# GTU-1-V1_1-20160516.net
KiCad netlist of a schematic drawn in Altium Designer
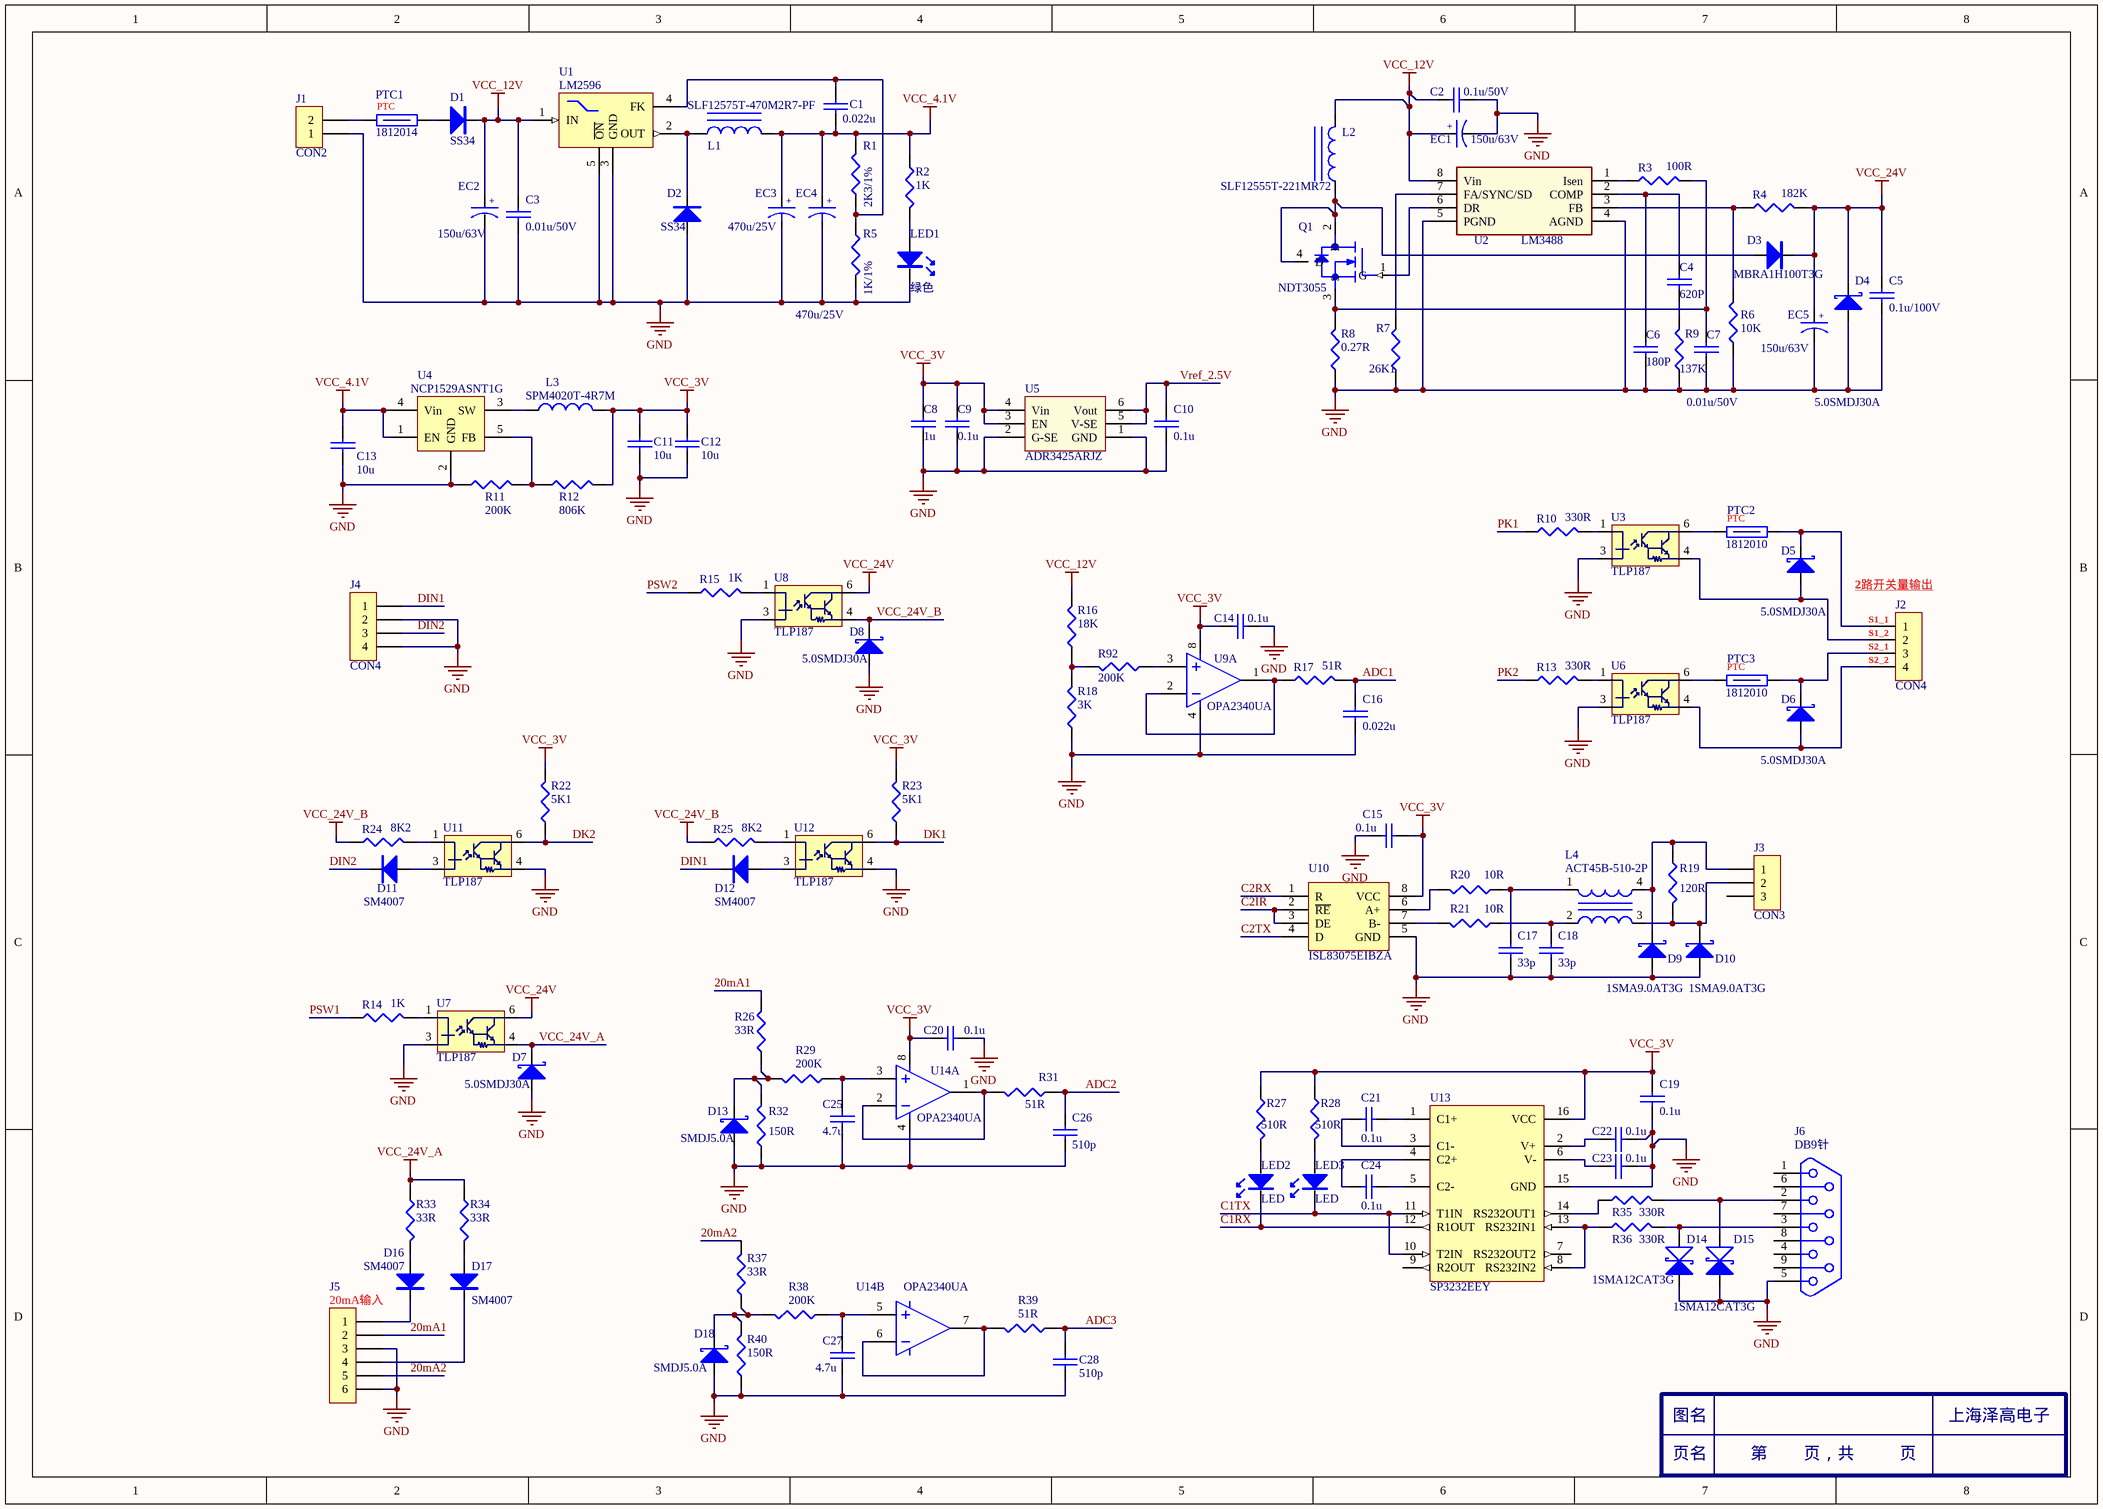
[diagram p0: GTU-1-V1.1-20160516.SCHDOC]

(export (version "E")
  (design (tool "Eeschema 10.0.6"))
  (components
    (comp (ref "3") (value "Component_1") (libsource (lib "*") (part "Component_1")))
    (comp (ref "C1")
      (value "0.022u")
      (footprint "0805-C")
      (description "Capacitor")
      (libsource (lib "STSCH-2012-11-22   ") (part "CAP"))
    )
    (comp (ref "C2")
      (value "0.1u/50V")
      (footprint "0805-C")
      (description "Capacitor")
      (fields (field (name "MFG") "TDK") (field (name "Comment") "0.1u"))
      (libsource (lib "SCHLIB-ZG-2016.01.18      ") (part "CAP"))
    )
    (comp (ref "C3")
      (value "0.01u/50V")
      (footprint "0805-C")
      (description "Capacitor")
      (libsource (lib "*") (part "CAP"))
    )
    (comp (ref "C4")
      (value "620P")
      (footprint "0805-C")
      (description "Capacitor")
      (fields (field (name "MFG") "TDK") (field (name "Comment") "0.1u"))
      (libsource (lib "SCHLIB-ZG-2016.01.18      ") (part "CAP"))
    )
    (comp (ref "C5")
      (value "0.1u/100V")
      (footprint "0805-C")
      (description "Capacitor")
      (fields (field (name "MFG") "TDK") (field (name "Comment") "0.1u"))
      (libsource (lib "SCHLIB-ZG-2016.01.18      ") (part "CAP"))
    )
    (comp (ref "C6")
      (value "180P")
      (footprint "0805-C")
      (description "Capacitor")
      (fields (field (name "MFG") "TDK") (field (name "Comment") "0.1u"))
      (libsource (lib "SCHLIB-ZG-2016.01.18      ") (part "CAP"))
    )
    (comp (ref "C7")
      (value "0.01u/50V")
      (footprint "0805-C")
      (description "Capacitor")
      (fields (field (name "MFG") "TDK") (field (name "Comment") "0.1u"))
      (libsource (lib "SCHLIB-ZG-2016.01.18      ") (part "CAP"))
    )
    (comp (ref "C8")
      (value "1u")
      (footprint "0805-C")
      (description "Capacitor")
      (fields (field (name "MFG") "TDK") (field (name "Comment") "0.1u"))
      (libsource (lib "SCHLIB-ZG-2015.12.11      ") (part "CAP"))
    )
    (comp (ref "C9")
      (value "0.1u")
      (footprint "0805-C")
      (description "Capacitor")
      (fields (field (name "MFG") "TDK"))
      (libsource (lib "SCHLIB-ZG-2015.12.11      ") (part "CAP"))
    )
    (comp (ref "C10")
      (value "0.1u")
      (footprint "0805-C")
      (description "Capacitor")
      (fields (field (name "MFG") "TDK"))
      (libsource (lib "SCHLIB-ZG-2015.12.11      ") (part "CAP"))
    )
    (comp (ref "C11")
      (value "10u")
      (footprint "0805-C")
      (description "Capacitor")
      (libsource (lib "STSCH-2012-08-02  ") (part "CAP"))
    )
    (comp (ref "C12")
      (value "10u")
      (footprint "0805-C")
      (description "Capacitor")
      (libsource (lib "STSCH-2012-08-02  ") (part "CAP"))
    )
    (comp (ref "C13")
      (value "10u")
      (footprint "0805-C")
      (description "Capacitor")
      (libsource (lib "STSCH-2012-02-16  ") (part "CAP"))
    )
    (comp (ref "C14")
      (value "0.1u")
      (footprint "0805-C")
      (description "Capacitor")
      (fields (field (name "MFG") "TDK"))
      (libsource (lib "SCHLIB-ZG-2016.01.18      ") (part "CAP"))
    )
    (comp (ref "C15")
      (value "0.1u")
      (footprint "0805-C")
      (description "Capacitor")
      (libsource (lib "") (part "CAP_1"))
    )
    (comp (ref "C16")
      (value "0.022u")
      (footprint "0805-C")
      (description "Capacitor")
      (fields (field (name "MFG") "TDK") (field (name "Comment") "0.1u"))
      (libsource (lib "SCHLIB-ZG-2016.01.18      ") (part "CAP"))
    )
    (comp (ref "C17")
      (value "33p")
      (footprint "0805-C")
      (description "Capacitor")
      (libsource (lib "STSCH-2013-09-02    ") (part "CAP"))
    )
    (comp (ref "C18")
      (value "33p")
      (footprint "0805-C")
      (description "Capacitor")
      (libsource (lib "STSCH-2013-09-02    ") (part "CAP"))
    )
    (comp (ref "C19")
      (value "0.1u")
      (footprint "0805-C")
      (description "Capacitor")
      (fields (field (name "MFG") "TDK"))
      (libsource (lib "SCHLIB-ZG-2015.12.11      ") (part "CAP"))
    )
    (comp (ref "C20")
      (value "0.1u")
      (footprint "0805-C")
      (description "Capacitor")
      (libsource (lib "STSCH-2011-12-16") (part "CAP"))
    )
    (comp (ref "C21")
      (value "0.1u")
      (footprint "0805-C")
      (description "Capacitor")
      (fields (field (name "MFG") "TDK"))
      (libsource (lib "SCHLIB-ZG-2015.12.11      ") (part "CAP"))
    )
    (comp (ref "C22")
      (value "0.1u")
      (footprint "0805-C")
      (description "Capacitor")
      (fields (field (name "MFG") "TDK"))
      (libsource (lib "SCHLIB-ZG-2015.12.11      ") (part "CAP"))
    )
    (comp (ref "C23")
      (value "0.1u")
      (footprint "0805-C")
      (description "Capacitor")
      (fields (field (name "MFG") "TDK"))
      (libsource (lib "SCHLIB-ZG-2015.12.11      ") (part "CAP"))
    )
    (comp (ref "C24")
      (value "0.1u")
      (footprint "0805-C")
      (description "Capacitor")
      (fields (field (name "MFG") "TDK"))
      (libsource (lib "SCHLIB-ZG-2015.12.11      ") (part "CAP"))
    )
    (comp (ref "C25")
      (value "4.7u")
      (footprint "0805-C")
      (description "Capacitor")
      (libsource (lib "STSCH-2011-12-16") (part "CAP"))
    )
    (comp (ref "C26")
      (value "510p")
      (footprint "0805-C")
      (description "Capacitor")
      (libsource (lib "STSCH-2011-12-16") (part "CAP"))
    )
    (comp (ref "C27")
      (value "4.7u")
      (footprint "0805-C")
      (description "Capacitor")
      (libsource (lib "STSCH-2011-12-16") (part "CAP"))
    )
    (comp (ref "C28")
      (value "510p")
      (footprint "0805-C")
      (description "Capacitor")
      (libsource (lib "STSCH-2011-12-16") (part "CAP"))
    )
    (comp (ref "D1")
      (value "SS34")
      (footprint "SMB")
      (description "Diode")
      (libsource (lib "STSCH-2012-11-08  ") (part "DIODE"))
    )
    (comp (ref "D2")
      (value "SS34")
      (footprint "SMB")
      (description "Diode")
      (libsource (lib "STSCH-2012-11-08  ") (part "DIODE"))
    )
    (comp (ref "D3")
      (value "MBRA1H100T3G")
      (footprint "SMA")
      (description "100V 70mA开关二极管")
      (fields (field (name "MFG") "Verical"))
      (libsource (lib "SCHLIB-ZG-2016.01.18      ") (part "1N4148"))
    )
    (comp (ref "D4")
      (value "5.0SMDJ30A")
      (footprint "SMC")
      (description "bidirectional 5000W TVS")
      (fields (field (name "MFG") "Littelfuse") (field (name "ALTIUM_VALUE") "5.0SMDJ30A"))
      (libsource (lib "SCHLIB-ZG-2016.01.18      ") (part "5.0SMDJxxA"))
    )
    (comp (ref "D5")
      (value "5.0SMDJ30A")
      (footprint "SMC")
      (description "bidirectional 5000W TVS")
      (fields (field (name "MFG") "Littelfuse"))
      (libsource (lib "SCHLIB-ZG-2016.01.18      ") (part "5.0SMDJxxA"))
    )
    (comp (ref "D6")
      (value "5.0SMDJ30A")
      (footprint "SMC")
      (description "bidirectional 5000W TVS")
      (fields (field (name "MFG") "Littelfuse"))
      (libsource (lib "SCHLIB-ZG-2016.01.18      ") (part "5.0SMDJxxA"))
    )
    (comp (ref "D7")
      (value "5.0SMDJ30A")
      (footprint "SMC")
      (description "bidirectional 5000W TVS")
      (fields (field (name "MFG") "Littelfuse"))
      (libsource (lib "SCHLIB-ZG-2016.01.18      ") (part "5.0SMDJxxA"))
    )
    (comp (ref "D8")
      (value "5.0SMDJ30A")
      (footprint "SMC")
      (description "bidirectional 5000W TVS")
      (fields (field (name "MFG") "Littelfuse"))
      (libsource (lib "SCHLIB-ZG-2016.01.18      ") (part "5.0SMDJxxA"))
    )
    (comp (ref "D9")
      (value "1SMAxxAT3G")
      (footprint "SMA")
      (description "Unidirectional 400W TVS")
      (fields (field (name "MFG") "ON-SEMI") (field (name "MFG_PN") "1SMA9.0AT3G"))
      (libsource (lib "SCHLIB-ZG-2016.03.14      ") (part "1SMAxxAT3G"))
    )
    (comp (ref "D10")
      (value "1SMAxxAT3G")
      (footprint "SMA")
      (description "Unidirectional 400W TVS")
      (fields (field (name "MFG") "ON-SEMI") (field (name "MFG_PN") "1SMA9.0AT3G"))
      (libsource (lib "SCHLIB-ZG-2016.03.14      ") (part "1SMAxxAT3G"))
    )
    (comp (ref "D11")
      (value "SM4007")
      (footprint "SMA")
      (description "Diode")
      (libsource (lib "*") (part "SMB"))
    )
    (comp (ref "D12")
      (value "SM4007")
      (footprint "SMA")
      (description "Diode")
      (libsource (lib "*") (part "SMB"))
    )
    (comp (ref "D13")
      (value "SMDJ5.0A")
      (footprint "SMC")
      (libsource (lib "STSCH-2013-02-22   ") (part "TVS"))
    )
    (comp (ref "D14")
      (value "1SMAxxCAT3G")
      (footprint "SMA")
      (description "400W双向TVS  ON Semconductor")
      (fields (field (name "MFG") "ON SEMI") (field (name "MFG-PN") "1SMA12CAT3G"))
      (libsource (lib "SCHLIB-ZG-2015.12.11      ") (part "1SMAxxCAT3G"))
    )
    (comp (ref "D15")
      (value "1SMA12CAT3G")
      (footprint "SMA")
      (description "400W双向TVS  ON Semconductor")
      (fields (field (name "MFG") "ON SEMI"))
      (libsource (lib "SCHLIB-ZG-2015.12.11      ") (part "1SMAxxCAT3G"))
    )
    (comp (ref "D16")
      (value "SM4007")
      (footprint "SMA")
      (description "Diode")
      (libsource (lib "*") (part "SMB"))
    )
    (comp (ref "D17")
      (value "SM4007")
      (footprint "SMA")
      (description "Diode")
      (libsource (lib "*") (part "SMB"))
    )
    (comp (ref "D18")
      (value "SMDJ5.0A")
      (footprint "SMC")
      (libsource (lib "STSCH-2013-02-22   ") (part "TVS"))
    )
    (comp (ref "EC1")
      (value "150u/63V")
      (footprint "SMD10X10.5")
      (description "铝电解电容")
      (fields (field (name "MFG") "RUBYCON"))
      (libsource (lib "SCHLIB-ZG-2015.12.11      ") (part "CAP Al"))
    )
    (comp (ref "EC2")
      (value "150u/63V")
      (footprint "SMD10X10.5")
      (description "铝电解电容")
      (fields (field (name "MFG") "RUBYCON") (field (name "Comment") "CAP Al"))
      (libsource (lib "SCHLIB-ZG-2015.12.11      ") (part "CAP Al"))
    )
    (comp (ref "EC3")
      (value "470u/25V")
      (footprint "SMD10X10.5")
      (libsource (lib "STSCH-2012-11-26   ") (part "CAP Al"))
    )
    (comp (ref "EC4")
      (value "470u/25V")
      (footprint "SMD10X10.5")
      (libsource (lib "STSCH-2012-11-26   ") (part "CAP Al"))
    )
    (comp (ref "EC5")
      (value "150u/63V")
      (footprint "SMD10X10.5")
      (description "铝电解电容")
      (fields (field (name "MFG") "RUBYCON"))
      (libsource (lib "SCHLIB-ZG-2015.12.11      ") (part "CAP Al"))
    )
    (comp (ref "J1")
      (value "CON2")
      (footprint "15EDGRC-3.81-2P")
      (description "Connector")
      (libsource (lib "SCHLIB-ZG-2015.12.11      ") (part "CON2"))
    )
    (comp (ref "J2")
      (value "CON4")
      (footprint "15EDGRC-3.81-4P")
      (description "Connector")
      (libsource (lib "") (part "CON4_1"))
    )
    (comp (ref "J3")
      (value "CON3")
      (footprint "15EDGRC-3.81-3P")
      (description "Connector")
      (libsource (lib "SCHLIB-ZG-2015.12.11      ") (part "CON3"))
    )
    (comp (ref "J4")
      (value "CON4")
      (footprint "15EDGRC-3.81-4P")
      (description "Connector")
      (libsource (lib "SCHLIB-ZG-2016.01.18      ") (part "CON4"))
    )
    (comp (ref "J5")
      (value "20mA输入")
      (footprint "15EDGRC-3.81-6P")
      (description "Connector")
      (libsource (lib "SCHLIB-ZG-2015.12.11      ") (part "CON6"))
    )
    (comp (ref "J6") (value "DB9针") (footprint "DB9RA/M") (libsource (lib "STSCH-2011-12-16") (part "DB9")))
    (comp (ref "L1")
      (value "SLF12575T-470M2R7-PF")
      (footprint "SLF12575")
      (libsource (lib "STSCH-2012-11-22   ") (part "INDUCTOR IRON"))
    )
    (comp (ref "L2")
      (value "SLF12555T-221MR72")
      (footprint "SLF12575")
      (description "12.5X12.5X7.5mm屏蔽功率电感")
      (fields (field (name "MFG") "TDK"))
      (libsource (lib "SCHLIB-ZG-2016.01.18      ") (part "SLF12575"))
    )
    (comp (ref "L3")
      (value "SPM4020T-4R7M")
      (footprint "SPM4020T-4R7M")
      (libsource (lib "STSCH-2012-08-02  ") (part "INDUCTOR"))
    )
    (comp (ref "L4")
      (value "ACT45B-510-2P")
      (footprint "ACT45B")
      (libsource (lib "STSCH-2013-09-02    ") (part "ACT45B-510-2P"))
    )
    (comp (ref "LED1") (value "绿色") (footprint "0805-LED") (libsource (lib "STSCH-20110618Q") (part "LED")))
    (comp (ref "LED2")
      (value "LED")
      (footprint "0805-LED")
      (libsource (lib "SCHLIB-ZG-2015.12.11      ") (part "LED"))
    )
    (comp (ref "LED3")
      (value "LED")
      (footprint "0805-LED")
      (libsource (lib "SCHLIB-ZG-2015.12.11      ") (part "LED"))
    )
    (comp (ref "PTC1")
      (value "1812014")
      (footprint "1812l075")
      (description "自恢复熔丝")
      (fields (field (name "MFG") "君耀"))
      (libsource (lib "SCHLIB-ZG-2016.01.18      ") (part "BK30-500"))
    )
    (comp (ref "PTC2")
      (value "1812010")
      (footprint "1812l075")
      (description "自恢复熔丝")
      (fields (field (name "MFG") "君耀"))
      (libsource (lib "SCHLIB-ZG-2016.01.18      ") (part "BK30-500"))
    )
    (comp (ref "PTC3")
      (value "1812010")
      (footprint "1812l075")
      (description "自恢复熔丝")
      (fields (field (name "MFG") "君耀"))
      (libsource (lib "SCHLIB-ZG-2016.01.18      ") (part "BK30-500"))
    )
    (comp (ref "Q1")
      (value "NDT3055")
      (description "TRANS CAN-N SOT223 2A 60V CMS")
      (fields (field (name "MFG") "FAIRCHILD"))
      (libsource (lib "SCHLIB-ZG-2016.01.18      ") (part "NDT3055"))
    )
    (comp (ref "R1")
      (value "2K3/1%")
      (footprint "0805-R")
      (libsource (lib "STSCH-2012-11-22   ") (part "RES"))
    )
    (comp (ref "R2") (value "1K") (footprint "0805-R") (libsource (lib "STSCH-20110618Q") (part "RES")))
    (comp (ref "R3")
      (value "100R")
      (footprint "0805-R")
      (description "电阻")
      (fields (field (name "MFG") "YAGO") (field (name "Comment") "RES"))
      (libsource (lib "SCHLIB-ZG-2016.01.18      ") (part "RES"))
    )
    (comp (ref "R4")
      (value "182K")
      (footprint "0805-R")
      (description "电阻")
      (fields (field (name "MFG") "YAGO") (field (name "Comment") "RES"))
      (libsource (lib "SCHLIB-ZG-2016.01.18      ") (part "RES"))
    )
    (comp (ref "R5")
      (value "1K/1%")
      (footprint "0805-R")
      (libsource (lib "STSCH-2012-11-22   ") (part "RES"))
    )
    (comp (ref "R6")
      (value "10K")
      (footprint "0805-R")
      (description "电阻")
      (fields (field (name "MFG") "YAGO") (field (name "Comment") "RES"))
      (libsource (lib "SCHLIB-ZG-2016.01.18      ") (part "RES"))
    )
    (comp (ref "R7")
      (value "26K1")
      (footprint "0805-R")
      (description "电阻")
      (fields (field (name "MFG") "YAGO") (field (name "Comment") "RES"))
      (libsource (lib "SCHLIB-ZG-2016.01.18      ") (part "RES"))
    )
    (comp (ref "R8")
      (value "0.27R")
      (footprint "0805-R")
      (description "电阻")
      (fields (field (name "MFG") "YAGO") (field (name "Comment") "RES"))
      (libsource (lib "SCHLIB-ZG-2016.01.18      ") (part "RES"))
    )
    (comp (ref "R9")
      (value "137K")
      (footprint "0805-R")
      (description "电阻")
      (fields (field (name "MFG") "YAGO") (field (name "Comment") "RES"))
      (libsource (lib "SCHLIB-ZG-2016.01.18      ") (part "RES"))
    )
    (comp (ref "R10")
      (value "330R")
      (footprint "0805-R")
      (description "电阻")
      (fields (field (name "MFG") "YAGO") (field (name "Comment") "RES"))
      (libsource (lib "SCHLIB-ZG-2016.01.18      ") (part "RES"))
    )
    (comp (ref "R11") (value "200K") (footprint "0805-R") (libsource (lib "STSCH-2012-08-02  ") (part "RES")))
    (comp (ref "R12") (value "806K") (footprint "0805-R") (libsource (lib "STSCH-2012-08-02  ") (part "RES")))
    (comp (ref "R13")
      (value "330R")
      (footprint "0805-R")
      (description "电阻")
      (fields (field (name "MFG") "YAGO") (field (name "Comment") "RES"))
      (libsource (lib "SCHLIB-ZG-2016.01.18      ") (part "RES"))
    )
    (comp (ref "R14")
      (value "1K")
      (footprint "0805-R")
      (description "电阻")
      (fields (field (name "MFG") "YAGO") (field (name "Comment") "RES"))
      (libsource (lib "SCHLIB-ZG-2016.01.18      ") (part "RES"))
    )
    (comp (ref "R15")
      (value "1K")
      (footprint "0805-R")
      (description "电阻")
      (fields (field (name "MFG") "YAGO") (field (name "Comment") "RES"))
      (libsource (lib "SCHLIB-ZG-2016.01.18      ") (part "RES"))
    )
    (comp (ref "R16")
      (value "18K")
      (footprint "0805-R")
      (description "电阻")
      (fields (field (name "MFG") "YAGO") (field (name "Comment") "RES"))
      (libsource (lib "SCHLIB-ZG-2016.01.18      ") (part "RES"))
    )
    (comp (ref "R17")
      (value "51R")
      (footprint "0805-R")
      (description "电阻")
      (fields (field (name "MFG") "YAGO") (field (name "Comment") "RES"))
      (libsource (lib "SCHLIB-ZG-2016.01.18      ") (part "RES"))
    )
    (comp (ref "R18")
      (value "3K")
      (footprint "0805-R")
      (description "电阻")
      (fields (field (name "MFG") "YAGO") (field (name "Comment") "RES"))
      (libsource (lib "SCHLIB-ZG-2016.01.18      ") (part "RES"))
    )
    (comp (ref "R19")
      (value "120R")
      (footprint "1210-R")
      (libsource (lib "STSCH-2013-09-02    ") (part "RES"))
    )
    (comp (ref "R20")
      (value "10R")
      (footprint "0805-R")
      (libsource (lib "STSCH-2013-09-02    ") (part "RES"))
    )
    (comp (ref "R21")
      (value "10R")
      (footprint "0805-R")
      (libsource (lib "STSCH-2013-09-02    ") (part "RES"))
    )
    (comp (ref "R22")
      (value "5K1")
      (footprint "0805-R")
      (description "电阻")
      (fields (field (name "MFG") "YAGO") (field (name "Comment") "RES"))
      (libsource (lib "SCHLIB-ZG-2016.01.18      ") (part "RES"))
    )
    (comp (ref "R23")
      (value "5K1")
      (footprint "0805-R")
      (description "电阻")
      (fields (field (name "MFG") "YAGO") (field (name "Comment") "RES"))
      (libsource (lib "SCHLIB-ZG-2016.01.18      ") (part "RES"))
    )
    (comp (ref "R24")
      (value "8K2")
      (footprint "0805-R")
      (description "电阻")
      (fields (field (name "MFG") "YAGO") (field (name "Comment") "RES"))
      (libsource (lib "SCHLIB-ZG-2016.01.18      ") (part "RES"))
    )
    (comp (ref "R25")
      (value "8K2")
      (footprint "0805-R")
      (description "电阻")
      (fields (field (name "MFG") "YAGO") (field (name "Comment") "RES"))
      (libsource (lib "SCHLIB-ZG-2016.01.18      ") (part "RES"))
    )
    (comp (ref "R26") (value "33R") (footprint "1210-R") (libsource (lib "STSCH-2011-12-16") (part "RES")))
    (comp (ref "R27")
      (value "510R")
      (footprint "0805-R")
      (description "电阻")
      (fields (field (name "MFG") "YAGO") (field (name "Comment") "RES"))
      (libsource (lib "SCHLIB-ZG-2016.01.18      ") (part "RES"))
    )
    (comp (ref "R28")
      (value "510R")
      (footprint "0805-R")
      (description "电阻")
      (fields (field (name "MFG") "YAGO") (field (name "Comment") "RES"))
      (libsource (lib "SCHLIB-ZG-2016.01.18      ") (part "RES"))
    )
    (comp (ref "R29") (value "200K") (footprint "0805-R") (libsource (lib "STSCH-2011-12-16") (part "RES")))
    (comp (ref "R31") (value "51R") (footprint "0805-R") (libsource (lib "STSCH-2011-12-16") (part "RES")))
    (comp (ref "R32") (value "150R") (footprint "1210-R") (libsource (lib "STSCH-2011-12-16") (part "RES")))
    (comp (ref "R33")
      (value "33R")
      (footprint "1210-R")
      (libsource (lib "STSCH-2013-09-02    ") (part "RES"))
    )
    (comp (ref "R34")
      (value "33R")
      (footprint "1210-R")
      (libsource (lib "STSCH-2013-09-02    ") (part "RES"))
    )
    (comp (ref "R35")
      (value "330R")
      (footprint "0805-R")
      (description "电阻")
      (fields (field (name "MFG") "YAGO") (field (name "Comment") "RES"))
      (libsource (lib "SCHLIB-ZG-2015.12.11      ") (part "RES"))
    )
    (comp (ref "R36")
      (value "330R")
      (footprint "0805-R")
      (description "电阻")
      (fields (field (name "MFG") "YAGO") (field (name "Comment") "RES"))
      (libsource (lib "SCHLIB-ZG-2015.12.11      ") (part "RES"))
    )
    (comp (ref "R37") (value "33R") (footprint "1210-R") (libsource (lib "STSCH-2011-12-16") (part "RES")))
    (comp (ref "R38") (value "200K") (footprint "0805-R") (libsource (lib "STSCH-2011-12-16") (part "RES")))
    (comp (ref "R39") (value "51R") (footprint "0805-R") (libsource (lib "STSCH-2011-12-16") (part "RES")))
    (comp (ref "R40") (value "150R") (footprint "1210-R") (libsource (lib "STSCH-2011-12-16") (part "RES")))
    (comp (ref "R92")
      (value "200K")
      (footprint "0805-R")
      (description "电阻")
      (fields (field (name "MFG") "YAGO") (field (name "Comment") "RES"))
      (libsource (lib "SCHLIB-ZG-2016.01.18      ") (part "RES"))
    )
    (comp (ref "U1")
      (value "LM2596")
      (footprint "D2PAK-5")
      (libsource (lib "STSCH-2012-11-22   ") (part "LM2596DSADJR4G"))
    )
    (comp (ref "U2")
      (value "LM3488")
      (description "ANALOG LM3488MM CMS")
      (fields (field (name "MFG") "NATIONAL SEMI"))
      (libsource (lib "SCHLIB-ZG-2016.01.18      ") (part "LM3488MM NOPB"))
    )
    (comp (ref "U3")
      (value "TLP187")
      (footprint "TLP187")
      (description "Darlington Photocouple Trsnsistor")
      (fields (field (name "MFG") "TOSHIBA"))
      (libsource (lib "SCHLIB-ZG-2016.01.18      ") (part "TLP187"))
    )
    (comp (ref "U4")
      (value "NCP1529ASNT1G")
      (footprint "SOT-23-5")
      (libsource (lib "STSCH-2012-08-02  ") (part "NCP1529ASNT1G"))
    )
    (comp (ref "U5")
      (value "ADR3425ARJZ")
      (footprint "SOT-23-6")
      (libsource (lib "轨旁检测-20151210") (part "ADR3430ARJZ"))
    )
    (comp (ref "U6")
      (value "TLP187")
      (footprint "TLP187")
      (description "Darlington Photocouple Trsnsistor")
      (fields (field (name "MFG") "TOSHIBA"))
      (libsource (lib "SCHLIB-ZG-2016.01.18      ") (part "TLP187"))
    )
    (comp (ref "U7")
      (value "TLP187")
      (footprint "TLP187")
      (description "Darlington Photocouple Trsnsistor")
      (fields (field (name "MFG") "TOSHIBA"))
      (libsource (lib "SCHLIB-ZG-2016.01.18      ") (part "TLP187"))
    )
    (comp (ref "U8")
      (value "TLP187")
      (footprint "TLP187")
      (description "Darlington Photocouple Trsnsistor")
      (fields (field (name "MFG") "TOSHIBA"))
      (libsource (lib "SCHLIB-ZG-2016.01.18      ") (part "TLP187"))
    )
    (comp (ref "U9")
      (value "OPA2340UA")
      (footprint "SO-8")
      (description "microPower, Rail-to-Rail  2 Operational Amplifiers")
      (fields (field (name "MFG") "TI"))
      (libsource (lib "SCHLIB-ZG-2016.01.18      ") (part "OPA2340"))
    )
    (comp (ref "U10") (value "ISL83075EIBZA") (footprint "SO-8") (libsource (lib "*") (part "75LBC184")))
    (comp (ref "U11")
      (value "TLP187")
      (footprint "TLP187")
      (description "Darlington Photocouple Trsnsistor")
      (fields (field (name "MFG") "TOSHIBA"))
      (libsource (lib "SCHLIB-ZG-2016.01.18      ") (part "TLP187"))
    )
    (comp (ref "U12")
      (value "TLP187")
      (footprint "TLP187")
      (description "Darlington Photocouple Trsnsistor")
      (fields (field (name "MFG") "TOSHIBA"))
      (libsource (lib "SCHLIB-ZG-2016.01.18      ") (part "TLP187"))
    )
    (comp (ref "U13")
      (value "SP3232EEY")
      (footprint "TSSOP-16")
      (description "+3.3V 1Mbps RS232收发器 SIPEX")
      (fields (field (name "MFG") "SIPEX"))
      (libsource (lib "SCHLIB-ZG-2015.12.11      ") (part "SP3232EEA"))
    )
    (comp (ref "U14")
      (value "OPA2340UA")
      (footprint "SO-8")
      (description "microPower, Rail-to-Rail  2 Operational Amplifiers")
      (fields (field (name "MFG") "TI"))
      (libsource (lib "SCHLIB-ZG-2016.01.18      ") (part "OPA2340"))
    )
  )
  (nets
    (net (code "1") (name "/20mA1") (class "Default")
      (node (ref "J5") (pin "2") (pinfunction "2_2") (pintype "passive"))
      (node (ref "R26") (pin "2") (pinfunction "2_2") (pintype "passive"))
    )
    (net (code "2") (name "/20mA2") (class "Default")
      (node (ref "J5") (pin "5") (pinfunction "5_5") (pintype "passive"))
      (node (ref "R37") (pin "2") (pinfunction "2_2") (pintype "passive"))
    )
    (net (code "3") (name "/ADC1") (class "Default")
      (node (ref "C16") (pin "1") (pinfunction "1_1") (pintype "passive"))
      (node (ref "R17") (pin "2") (pinfunction "2_2") (pintype "passive"))
    )
    (net (code "4") (name "/ADC2") (class "Default")
      (node (ref "C26") (pin "1") (pinfunction "1_1") (pintype "passive"))
      (node (ref "R31") (pin "1") (pinfunction "1_1") (pintype "passive"))
    )
    (net (code "5") (name "/ADC3") (class "Default")
      (node (ref "C28") (pin "1") (pinfunction "1_1") (pintype "passive"))
      (node (ref "R39") (pin "1") (pinfunction "1_1") (pintype "passive"))
    )
    (net (code "6") (name "/C1RX") (class "Default")
      (node (ref "LED2") (pin "2") (pintype "passive"))
      (node (ref "U13") (pin "12") (pinfunction "R1OUT_12") (pintype "output"))
    )
    (net (code "7") (name "/C1TX") (class "Default")
      (node (ref "LED3") (pin "2") (pintype "passive"))
      (node (ref "U13") (pin "10") (pinfunction "T2IN_10") (pintype "input"))
      (node (ref "U13") (pin "11") (pinfunction "T1IN_11") (pintype "input"))
    )
    (net (code "8") (name "/C2IR") (class "Default")
      (node (ref "U10") (pin "2") (pinfunction "~{RE}_2") (pintype "passive"))
      (node (ref "U10") (pin "3") (pinfunction "DE_3") (pintype "passive"))
    )
    (net (code "9") (name "/C2RX") (class "Default")
      (node (ref "U10") (pin "1") (pinfunction "R_1") (pintype "passive"))
    )
    (net (code "10") (name "/C2TX") (class "Default")
      (node (ref "U10") (pin "4") (pinfunction "D_4") (pintype "passive"))
    )
    (net (code "11") (name "/DIN1") (class "Default")
      (node (ref "D12") (pin "K") (pinfunction "K_K") (pintype "passive"))
      (node (ref "J4") (pin "1") (pinfunction "1_1") (pintype "passive"))
    )
    (net (code "12") (name "/DIN2") (class "Default")
      (node (ref "D11") (pin "K") (pinfunction "K_K") (pintype "passive"))
      (node (ref "J4") (pin "3") (pinfunction "3_3") (pintype "passive"))
    )
    (net (code "13") (name "/DK1") (class "Default")
      (node (ref "R23") (pin "1") (pinfunction "1_1") (pintype "passive"))
      (node (ref "U12") (pin "6") (pinfunction "6_6") (pintype "passive"))
    )
    (net (code "14") (name "/DK2") (class "Default")
      (node (ref "R22") (pin "1") (pinfunction "1_1") (pintype "passive"))
      (node (ref "U11") (pin "6") (pinfunction "6_6") (pintype "passive"))
    )
    (net (code "15") (name "/PK1") (class "Default")
      (node (ref "R10") (pin "1") (pinfunction "1_1") (pintype "passive"))
    )
    (net (code "16") (name "/PK2") (class "Default")
      (node (ref "R13") (pin "1") (pinfunction "1_1") (pintype "passive"))
    )
    (net (code "17") (name "/PSW1") (class "Default")
      (node (ref "R14") (pin "1") (pinfunction "1_1") (pintype "passive"))
    )
    (net (code "18") (name "/PSW2") (class "Default")
      (node (ref "R15") (pin "1") (pinfunction "1_1") (pintype "passive"))
    )
    (net (code "19") (name "/Vref_2.5V") (class "Default")
      (node (ref "C10") (pin "1") (pinfunction "1_1") (pintype "passive"))
      (node (ref "U5") (pin "5") (pinfunction "V-SE_5") (pintype "passive"))
      (node (ref "U5") (pin "6") (pinfunction "Vout_6") (pintype "passive"))
    )
    (net (code "20") (name "GND") (class "Default")
      (node (ref "C10") (pin "2") (pinfunction "2_2") (pintype "passive"))
      (node (ref "C11") (pin "2") (pinfunction "2_2") (pintype "passive"))
      (node (ref "C12") (pin "2") (pinfunction "2_2") (pintype "passive"))
      (node (ref "C13") (pin "2") (pinfunction "2_2") (pintype "passive"))
      (node (ref "C14") (pin "2") (pinfunction "2_2") (pintype "passive"))
      (node (ref "C15") (pin "2") (pinfunction "2_2") (pintype "passive"))
      (node (ref "C16") (pin "2") (pinfunction "2_2") (pintype "passive"))
      (node (ref "C17") (pin "2") (pinfunction "2_2") (pintype "passive"))
      (node (ref "C18") (pin "2") (pinfunction "2_2") (pintype "passive"))
      (node (ref "C19") (pin "1") (pinfunction "1_1") (pintype "passive"))
      (node (ref "C2") (pin "2") (pinfunction "2_2") (pintype "passive"))
      (node (ref "C20") (pin "2") (pinfunction "2_2") (pintype "passive"))
      (node (ref "C22") (pin "1") (pinfunction "1_1") (pintype "passive"))
      (node (ref "C23") (pin "1") (pinfunction "1_1") (pintype "passive"))
      (node (ref "C25") (pin "2") (pinfunction "2_2") (pintype "passive"))
      (node (ref "C26") (pin "2") (pinfunction "2_2") (pintype "passive"))
      (node (ref "C27") (pin "2") (pinfunction "2_2") (pintype "passive"))
      (node (ref "C28") (pin "2") (pinfunction "2_2") (pintype "passive"))
      (node (ref "C3") (pin "2") (pinfunction "2_2") (pintype "passive"))
      (node (ref "C5") (pin "2") (pinfunction "2_2") (pintype "passive"))
      (node (ref "C6") (pin "2") (pinfunction "2_2") (pintype "passive"))
      (node (ref "C7") (pin "2") (pinfunction "2_2") (pintype "passive"))
      (node (ref "C8") (pin "2") (pinfunction "2_2") (pintype "passive"))
      (node (ref "C9") (pin "2") (pinfunction "2_2") (pintype "passive"))
      (node (ref "D10") (pin "A") (pinfunction "A_A") (pintype "passive"))
      (node (ref "D13") (pin "A") (pinfunction "A_A") (pintype "passive"))
      (node (ref "D14") (pin "A") (pinfunction "A_A") (pintype "passive"))
      (node (ref "D15") (pin "A") (pinfunction "A_A") (pintype "passive"))
      (node (ref "D18") (pin "A") (pinfunction "A_A") (pintype "passive"))
      (node (ref "D2") (pin "A") (pinfunction "A_A") (pintype "passive"))
      (node (ref "D4") (pin "A") (pinfunction "A_A") (pintype "passive"))
      (node (ref "D7") (pin "A") (pinfunction "A_A") (pintype "passive"))
      (node (ref "D8") (pin "A") (pinfunction "A_A") (pintype "passive"))
      (node (ref "D9") (pin "A") (pinfunction "A_A") (pintype "passive"))
      (node (ref "EC1") (pin "2") (pinfunction "2_2") (pintype "passive"))
      (node (ref "EC2") (pin "2") (pinfunction "2_2") (pintype "passive"))
      (node (ref "EC3") (pin "2") (pinfunction "2_2") (pintype "passive"))
      (node (ref "EC4") (pin "2") (pinfunction "2_2") (pintype "passive"))
      (node (ref "EC5") (pin "2") (pinfunction "2_2") (pintype "passive"))
      (node (ref "J1") (pin "1") (pinfunction "1_1") (pintype "passive"))
      (node (ref "J4") (pin "2") (pinfunction "2_2") (pintype "passive"))
      (node (ref "J4") (pin "4") (pinfunction "4_4") (pintype "passive"))
      (node (ref "J5") (pin "3") (pinfunction "3_3") (pintype "passive"))
      (node (ref "J5") (pin "6") (pinfunction "6_6") (pintype "passive"))
      (node (ref "J6") (pin "5") (pinfunction "5_5") (pintype "passive"))
      (node (ref "LED1") (pin "2") (pintype "passive"))
      (node (ref "R11") (pin "1") (pinfunction "1_1") (pintype "passive"))
      (node (ref "R18") (pin "1") (pinfunction "1_1") (pintype "passive"))
      (node (ref "R32") (pin "1") (pinfunction "1_1") (pintype "passive"))
      (node (ref "R40") (pin "1") (pinfunction "1_1") (pintype "passive"))
      (node (ref "R5") (pin "2") (pinfunction "2_2") (pintype "passive"))
      (node (ref "R6") (pin "1") (pinfunction "1_1") (pintype "passive"))
      (node (ref "R7") (pin "1") (pinfunction "1_1") (pintype "passive"))
      (node (ref "R8") (pin "1") (pinfunction "1_1") (pintype "passive"))
      (node (ref "R9") (pin "1") (pinfunction "1_1") (pintype "passive"))
      (node (ref "U1") (pin "3") (pinfunction "GND_3") (pintype "passive"))
      (node (ref "U1") (pin "5") (pinfunction "~{ON}_5") (pintype "passive"))
      (node (ref "U10") (pin "5") (pinfunction "GND_5") (pintype "power_in"))
      (node (ref "U11") (pin "4") (pinfunction "4_4") (pintype "passive"))
      (node (ref "U12") (pin "4") (pinfunction "4_4") (pintype "passive"))
      (node (ref "U13") (pin "15") (pinfunction "GND_15") (pintype "power_in"))
      (node (ref "U14") (pin "4") (pintype "passive"))
      (node (ref "U2") (pin "4") (pinfunction "AGND_4") (pintype "power_in"))
      (node (ref "U2") (pin "5") (pinfunction "PGND_5") (pintype "power_in"))
      (node (ref "U3") (pin "3") (pinfunction "3_3") (pintype "passive"))
      (node (ref "U4") (pin "2") (pinfunction "GND_2") (pintype "passive"))
      (node (ref "U5") (pin "1") (pinfunction "GND_1") (pintype "passive"))
      (node (ref "U5") (pin "2") (pinfunction "G-SE_2") (pintype "passive"))
      (node (ref "U6") (pin "3") (pinfunction "3_3") (pintype "passive"))
      (node (ref "U7") (pin "3") (pinfunction "3_3") (pintype "passive"))
      (node (ref "U8") (pin "3") (pinfunction "3_3") (pintype "passive"))
      (node (ref "U9") (pin "4") (pintype "passive"))
    )
    (net (code "21") (name "Net-(C4-Pad2)") (class "Default")
      (node (ref "C4") (pin "2") (pinfunction "2_2") (pintype "passive"))
      (node (ref "R9") (pin "2") (pinfunction "2_2") (pintype "passive"))
    )
    (net (code "22") (name "Net-(C17-Pad1)") (class "Default")
      (node (ref "C17") (pin "1") (pinfunction "1_1") (pintype "passive"))
      (node (ref "L4") (pin "1") (pinfunction "1_1") (pintype "passive"))
      (node (ref "R20") (pin "1") (pinfunction "1_1") (pintype "passive"))
    )
    (net (code "23") (name "Net-(C18-Pad1)") (class "Default")
      (node (ref "C18") (pin "1") (pinfunction "1_1") (pintype "passive"))
      (node (ref "L4") (pin "2") (pinfunction "2_2") (pintype "passive"))
      (node (ref "R21") (pin "1") (pinfunction "1_1") (pintype "passive"))
    )
    (net (code "24") (name "Net-(C25-Pad1)") (class "Default")
      (node (ref "C25") (pin "1") (pinfunction "1_1") (pintype "passive"))
      (node (ref "R29") (pin "1") (pinfunction "1_1") (pintype "passive"))
      (node (ref "U14") (pin "3") (pintype "passive"))
    )
    (net (code "25") (name "Net-(C27-Pad1)") (class "Default")
      (node (ref "C27") (pin "1") (pinfunction "1_1") (pintype "passive"))
      (node (ref "R38") (pin "1") (pinfunction "1_1") (pintype "passive"))
      (node (ref "U14") (pin "5") (pintype "passive"))
    )
    (net (code "26") (name "Net-(D1-PadA)") (class "Default")
      (node (ref "D1") (pin "A") (pinfunction "A_A") (pintype "passive"))
      (node (ref "PTC1") (pin "2") (pinfunction "2_2") (pintype "passive"))
    )
    (net (code "27") (name "Net-(D3-PadA)") (class "Default")
      (node (ref "D3") (pin "A") (pinfunction "A_A") (pintype "passive"))
      (node (ref "L2") (pin "1") (pinfunction "1_1") (pintype "passive"))
      (node (ref "Q1") (pin "2") (pinfunction "D_2") (pintype "power_in"))
      (node (ref "Q1") (pin "4") (pinfunction "D_4") (pintype "power_in"))
    )
    (net (code "28") (name "Net-(D5-PadA)") (class "Default")
      (node (ref "D5") (pin "A") (pinfunction "A_A") (pintype "passive"))
      (node (ref "J2") (pin "2") (pinfunction "2_2") (pintype "passive"))
      (node (ref "U3") (pin "4") (pinfunction "4_4") (pintype "passive"))
    )
    (net (code "29") (name "Net-(D5-PadK)") (class "Default")
      (node (ref "D5") (pin "K") (pinfunction "K_K") (pintype "passive"))
      (node (ref "J2") (pin "1") (pinfunction "1_1") (pintype "passive"))
      (node (ref "PTC2") (pin "2") (pinfunction "2_2") (pintype "passive"))
    )
    (net (code "30") (name "Net-(D6-PadA)") (class "Default")
      (node (ref "D6") (pin "A") (pinfunction "A_A") (pintype "passive"))
      (node (ref "J2") (pin "4") (pinfunction "4_4") (pintype "passive"))
      (node (ref "U6") (pin "4") (pinfunction "4_4") (pintype "passive"))
    )
    (net (code "31") (name "Net-(D6-PadK)") (class "Default")
      (node (ref "D6") (pin "K") (pinfunction "K_K") (pintype "passive"))
      (node (ref "J2") (pin "3") (pinfunction "3_3") (pintype "passive"))
      (node (ref "PTC3") (pin "2") (pinfunction "2_2") (pintype "passive"))
    )
    (net (code "32") (name "Net-(D9-PadK)") (class "Default")
      (node (ref "D9") (pin "K") (pinfunction "K_K") (pintype "passive"))
      (node (ref "J3") (pin "1") (pinfunction "1_1") (pintype "passive"))
      (node (ref "L4") (pin "4") (pinfunction "4_4") (pintype "passive"))
      (node (ref "R19") (pin "1") (pinfunction "1_1") (pintype "passive"))
    )
    (net (code "33") (name "Net-(D10-PadK)") (class "Default")
      (node (ref "D10") (pin "K") (pinfunction "K_K") (pintype "passive"))
      (node (ref "J3") (pin "2") (pinfunction "2_2") (pintype "passive"))
      (node (ref "L4") (pin "3") (pinfunction "3_3") (pintype "passive"))
      (node (ref "R19") (pin "2") (pinfunction "2_2") (pintype "passive"))
    )
    (net (code "34") (name "Net-(D11-PadA)") (class "Default")
      (node (ref "D11") (pin "A") (pinfunction "A_A") (pintype "passive"))
      (node (ref "U11") (pin "3") (pinfunction "3_3") (pintype "passive"))
    )
    (net (code "35") (name "Net-(D12-PadA)") (class "Default")
      (node (ref "D12") (pin "A") (pinfunction "A_A") (pintype "passive"))
      (node (ref "U12") (pin "3") (pinfunction "3_3") (pintype "passive"))
    )
    (net (code "36") (name "Net-(D13-PadK)") (class "Default")
      (node (ref "D13") (pin "K") (pinfunction "K_K") (pintype "passive"))
      (node (ref "R26") (pin "1") (pinfunction "1_1") (pintype "passive"))
      (node (ref "R29") (pin "2") (pinfunction "2_2") (pintype "passive"))
      (node (ref "R32") (pin "2") (pinfunction "2_2") (pintype "passive"))
    )
    (net (code "37") (name "Net-(D14-PadK)") (class "Default")
      (node (ref "D14") (pin "K") (pinfunction "K_K") (pintype "passive"))
      (node (ref "J6") (pin "3") (pinfunction "3_3") (pintype "passive"))
      (node (ref "R36") (pin "1") (pinfunction "1_1") (pintype "passive"))
    )
    (net (code "38") (name "Net-(D15-PadK)") (class "Default")
      (node (ref "D15") (pin "K") (pinfunction "K_K") (pintype "passive"))
      (node (ref "J6") (pin "2") (pinfunction "2_2") (pintype "passive"))
      (node (ref "R35") (pin "1") (pinfunction "1_1") (pintype "passive"))
    )
    (net (code "39") (name "Net-(D16-PadA)") (class "Default")
      (node (ref "D16") (pin "A") (pinfunction "A_A") (pintype "passive"))
      (node (ref "R33") (pin "2") (pinfunction "2_2") (pintype "passive"))
    )
    (net (code "40") (name "Net-(D16-PadK)") (class "Default")
      (node (ref "D16") (pin "K") (pinfunction "K_K") (pintype "passive"))
      (node (ref "J5") (pin "1") (pinfunction "1_1") (pintype "passive"))
    )
    (net (code "41") (name "Net-(D17-PadA)") (class "Default")
      (node (ref "D17") (pin "A") (pinfunction "A_A") (pintype "passive"))
      (node (ref "R34") (pin "2") (pinfunction "2_2") (pintype "passive"))
    )
    (net (code "42") (name "Net-(D17-PadK)") (class "Default")
      (node (ref "D17") (pin "K") (pinfunction "K_K") (pintype "passive"))
      (node (ref "J5") (pin "4") (pinfunction "4_4") (pintype "passive"))
    )
    (net (code "43") (name "Net-(D18-PadK)") (class "Default")
      (node (ref "D18") (pin "K") (pinfunction "K_K") (pintype "passive"))
      (node (ref "R37") (pin "1") (pinfunction "1_1") (pintype "passive"))
      (node (ref "R38") (pin "2") (pinfunction "2_2") (pintype "passive"))
      (node (ref "R40") (pin "2") (pinfunction "2_2") (pintype "passive"))
    )
    (net (code "44") (name "Net-(J1-Pad2)") (class "Default")
      (node (ref "J1") (pin "2") (pinfunction "2_2") (pintype "passive"))
      (node (ref "PTC1") (pin "1") (pinfunction "1_1") (pintype "passive"))
    )
    (net (code "45") (name "Net-(LED1-Pad1)") (class "Default")
      (node (ref "LED1") (pin "1") (pintype "passive"))
      (node (ref "R2") (pin "2") (pinfunction "2_2") (pintype "passive"))
    )
    (net (code "46") (name "Net-(LED2-Pad1)") (class "Default")
      (node (ref "LED2") (pin "1") (pintype "passive"))
      (node (ref "R27") (pin "1") (pinfunction "1_1") (pintype "passive"))
    )
    (net (code "47") (name "Net-(LED3-Pad1)") (class "Default")
      (node (ref "LED3") (pin "1") (pintype "passive"))
      (node (ref "R28") (pin "1") (pinfunction "1_1") (pintype "passive"))
    )
    (net (code "48") (name "Net-(PTC2-Pad1)") (class "Default")
      (node (ref "PTC2") (pin "1") (pinfunction "1_1") (pintype "passive"))
      (node (ref "U3") (pin "6") (pinfunction "6_6") (pintype "passive"))
    )
    (net (code "49") (name "Net-(PTC3-Pad1)") (class "Default")
      (node (ref "PTC3") (pin "1") (pinfunction "1_1") (pintype "passive"))
      (node (ref "U6") (pin "6") (pinfunction "6_6") (pintype "passive"))
    )
    (net (code "50") (name "Net-(Q1-G)") (class "Default")
      (node (ref "Q1") (pin "1") (pinfunction "G_1") (pintype "input"))
      (node (ref "U2") (pin "6") (pinfunction "DR_6") (pintype "passive"))
    )
    (net (code "51") (name "Net-(Q1-S)") (class "Default")
      (node (ref "C7") (pin "1") (pinfunction "1_1") (pintype "passive"))
      (node (ref "Q1") (pin "3") (pinfunction "S_3") (pintype "passive"))
      (node (ref "R3") (pin "2") (pinfunction "2_2") (pintype "passive"))
      (node (ref "R8") (pin "2") (pinfunction "2_2") (pintype "passive"))
    )
    (net (code "52") (name "Net-(R10-Pad2)") (class "Default")
      (node (ref "R10") (pin "2") (pinfunction "2_2") (pintype "passive"))
      (node (ref "U3") (pin "1") (pinfunction "1_1") (pintype "passive"))
    )
    (net (code "53") (name "Net-(R13-Pad2)") (class "Default")
      (node (ref "R13") (pin "2") (pinfunction "2_2") (pintype "passive"))
      (node (ref "U6") (pin "1") (pinfunction "1_1") (pintype "passive"))
    )
    (net (code "54") (name "Net-(R14-Pad2)") (class "Default")
      (node (ref "R14") (pin "2") (pinfunction "2_2") (pintype "passive"))
      (node (ref "U7") (pin "1") (pinfunction "1_1") (pintype "passive"))
    )
    (net (code "55") (name "Net-(R15-Pad2)") (class "Default")
      (node (ref "R15") (pin "2") (pinfunction "2_2") (pintype "passive"))
      (node (ref "U8") (pin "1") (pinfunction "1_1") (pintype "passive"))
    )
    (net (code "56") (name "Net-(R16-Pad1)") (class "Default")
      (node (ref "R16") (pin "1") (pinfunction "1_1") (pintype "passive"))
      (node (ref "R18") (pin "2") (pinfunction "2_2") (pintype "passive"))
      (node (ref "R92") (pin "2") (pinfunction "2_2") (pintype "passive"))
    )
    (net (code "57") (name "Net-(R17-Pad1)") (class "Default")
      (node (ref "R17") (pin "1") (pinfunction "1_1") (pintype "passive"))
      (node (ref "U9") (pin "1") (pintype "passive"))
      (node (ref "U9") (pin "2") (pintype "passive"))
    )
    (net (code "58") (name "Net-(R24-Pad2)") (class "Default")
      (node (ref "R24") (pin "2") (pinfunction "2_2") (pintype "passive"))
      (node (ref "U11") (pin "1") (pinfunction "1_1") (pintype "passive"))
    )
    (net (code "59") (name "Net-(R25-Pad2)") (class "Default")
      (node (ref "R25") (pin "2") (pinfunction "2_2") (pintype "passive"))
      (node (ref "U12") (pin "1") (pinfunction "1_1") (pintype "passive"))
    )
    (net (code "60") (name "Net-(R31-Pad2)") (class "Default")
      (node (ref "R31") (pin "2") (pinfunction "2_2") (pintype "passive"))
      (node (ref "U14") (pin "1") (pintype "passive"))
      (node (ref "U14") (pin "2") (pintype "passive"))
    )
    (net (code "61") (name "Net-(R39-Pad2)") (class "Default")
      (node (ref "R39") (pin "2") (pinfunction "2_2") (pintype "passive"))
      (node (ref "U14") (pin "6") (pintype "passive"))
      (node (ref "U14") (pin "7") (pintype "passive"))
    )
    (net (code "62") (name "Net-(R92-Pad1)") (class "Default")
      (node (ref "R92") (pin "1") (pinfunction "1_1") (pintype "passive"))
      (node (ref "U9") (pin "3") (pintype "passive"))
    )
    (net (code "63") (name "Net-(U1-FK)") (class "Default")
      (node (ref "C1") (pin "2") (pinfunction "2_2") (pintype "passive"))
      (node (ref "R1") (pin "1") (pinfunction "1_1") (pintype "passive"))
      (node (ref "R5") (pin "1") (pinfunction "1_1") (pintype "passive"))
      (node (ref "U1") (pin "4") (pinfunction "FK_4") (pintype "passive"))
    )
    (net (code "64") (name "Net-(U1-OUT)") (class "Default")
      (node (ref "D2") (pin "K") (pinfunction "K_K") (pintype "passive"))
      (node (ref "L1") (pin "1") (pinfunction "1_1") (pintype "passive"))
      (node (ref "U1") (pin "2") (pinfunction "OUT_2") (pintype "output"))
    )
    (net (code "65") (name "Net-(U2-COMP)") (class "Default")
      (node (ref "C4") (pin "1") (pinfunction "1_1") (pintype "passive"))
      (node (ref "C6") (pin "1") (pinfunction "1_1") (pintype "passive"))
      (node (ref "U2") (pin "2") (pinfunction "COMP_2") (pintype "passive"))
    )
    (net (code "66") (name "Net-(U2-FA{slash}SYNC{slash}SD)") (class "Default")
      (node (ref "R7") (pin "2") (pinfunction "2_2") (pintype "passive"))
      (node (ref "U2") (pin "7") (pinfunction "FA/SYNC/SD_7") (pintype "passive"))
    )
    (net (code "67") (name "Net-(U2-FB)") (class "Default")
      (node (ref "R4") (pin "1") (pinfunction "1_1") (pintype "passive"))
      (node (ref "R6") (pin "2") (pinfunction "2_2") (pintype "passive"))
      (node (ref "U2") (pin "3") (pinfunction "FB_3") (pintype "passive"))
    )
    (net (code "68") (name "Net-(U2-Isen)") (class "Default")
      (node (ref "R3") (pin "1") (pinfunction "1_1") (pintype "passive"))
      (node (ref "U2") (pin "1") (pinfunction "Isen_1") (pintype "passive"))
    )
    (net (code "69") (name "Net-(U4-FB)") (class "Default")
      (node (ref "R11") (pin "2") (pinfunction "2_2") (pintype "passive"))
      (node (ref "R12") (pin "1") (pinfunction "1_1") (pintype "passive"))
      (node (ref "U4") (pin "5") (pinfunction "FB_5") (pintype "passive"))
    )
    (net (code "70") (name "Net-(U4-SW)") (class "Default")
      (node (ref "L3") (pin "1") (pinfunction "1_1") (pintype "passive"))
      (node (ref "U4") (pin "3") (pinfunction "SW_3") (pintype "passive"))
    )
    (net (code "71") (name "Net-(U10-A+)") (class "Default")
      (node (ref "R20") (pin "2") (pinfunction "2_2") (pintype "passive"))
      (node (ref "U10") (pin "6") (pinfunction "A+_6") (pintype "passive"))
    )
    (net (code "72") (name "Net-(U10-B-)") (class "Default")
      (node (ref "R21") (pin "2") (pinfunction "2_2") (pintype "passive"))
      (node (ref "U10") (pin "7") (pinfunction "B-_7") (pintype "passive"))
    )
    (net (code "73") (name "Net-(U13-C1+)") (class "Default")
      (node (ref "C21") (pin "1") (pinfunction "1_1") (pintype "passive"))
      (node (ref "U13") (pin "1") (pinfunction "C1+_1") (pintype "passive"))
    )
    (net (code "74") (name "Net-(U13-C1-)") (class "Default")
      (node (ref "C21") (pin "2") (pinfunction "2_2") (pintype "passive"))
      (node (ref "U13") (pin "3") (pinfunction "C1-_3") (pintype "passive"))
    )
    (net (code "75") (name "Net-(U13-C2+)") (class "Default")
      (node (ref "C24") (pin "2") (pinfunction "2_2") (pintype "passive"))
      (node (ref "U13") (pin "4") (pinfunction "C2+_4") (pintype "passive"))
    )
    (net (code "76") (name "Net-(U13-C2-)") (class "Default")
      (node (ref "C24") (pin "1") (pinfunction "1_1") (pintype "passive"))
      (node (ref "U13") (pin "5") (pinfunction "C2-_5") (pintype "passive"))
    )
    (net (code "77") (name "Net-(U13-RS232IN1)") (class "Default")
      (node (ref "R36") (pin "2") (pinfunction "2_2") (pintype "passive"))
      (node (ref "U13") (pin "13") (pinfunction "RS232IN1_13") (pintype "input"))
      (node (ref "U13") (pin "8") (pinfunction "RS232IN2_8") (pintype "input"))
    )
    (net (code "78") (name "Net-(U13-RS232OUT1)") (class "Default")
      (node (ref "R35") (pin "2") (pinfunction "2_2") (pintype "passive"))
      (node (ref "U13") (pin "14") (pinfunction "RS232OUT1_14") (pintype "output"))
    )
    (net (code "79") (name "Net-(U13-V+)") (class "Default")
      (node (ref "C22") (pin "2") (pinfunction "2_2") (pintype "passive"))
      (node (ref "U13") (pin "2") (pinfunction "V+_2") (pintype "passive"))
    )
    (net (code "80") (name "Net-(U13-V-)") (class "Default")
      (node (ref "C23") (pin "2") (pinfunction "2_2") (pintype "passive"))
      (node (ref "U13") (pin "6") (pinfunction "V-_6") (pintype "passive"))
    )
    (net (code "81") (name "VCC_3V") (class "Default")
      (node (ref "C11") (pin "1") (pinfunction "1_1") (pintype "passive"))
      (node (ref "C12") (pin "1") (pinfunction "1_1") (pintype "passive"))
      (node (ref "C14") (pin "1") (pinfunction "1_1") (pintype "passive"))
      (node (ref "C15") (pin "1") (pinfunction "1_1") (pintype "passive"))
      (node (ref "C19") (pin "2") (pinfunction "2_2") (pintype "passive"))
      (node (ref "C20") (pin "1") (pinfunction "1_1") (pintype "passive"))
      (node (ref "C8") (pin "1") (pinfunction "1_1") (pintype "passive"))
      (node (ref "C9") (pin "1") (pinfunction "1_1") (pintype "passive"))
      (node (ref "L3") (pin "2") (pinfunction "2_2") (pintype "passive"))
      (node (ref "R12") (pin "2") (pinfunction "2_2") (pintype "passive"))
      (node (ref "R22") (pin "2") (pinfunction "2_2") (pintype "passive"))
      (node (ref "R23") (pin "2") (pinfunction "2_2") (pintype "passive"))
      (node (ref "R27") (pin "2") (pinfunction "2_2") (pintype "passive"))
      (node (ref "R28") (pin "2") (pinfunction "2_2") (pintype "passive"))
      (node (ref "U10") (pin "8") (pinfunction "VCC_8") (pintype "power_in"))
      (node (ref "U13") (pin "16") (pinfunction "VCC_16") (pintype "power_in"))
      (node (ref "U14") (pin "8") (pintype "passive"))
      (node (ref "U5") (pin "3") (pinfunction "EN_3") (pintype "passive"))
      (node (ref "U5") (pin "4") (pinfunction "Vin_4") (pintype "passive"))
      (node (ref "U9") (pin "8") (pintype "passive"))
    )
    (net (code "82") (name "VCC_4.1V") (class "Default")
      (node (ref "C1") (pin "1") (pinfunction "1_1") (pintype "passive"))
      (node (ref "C13") (pin "1") (pinfunction "1_1") (pintype "passive"))
      (node (ref "EC3") (pin "1") (pinfunction "1_1") (pintype "passive"))
      (node (ref "EC4") (pin "1") (pinfunction "1_1") (pintype "passive"))
      (node (ref "L1") (pin "2") (pinfunction "2_2") (pintype "passive"))
      (node (ref "R1") (pin "2") (pinfunction "2_2") (pintype "passive"))
      (node (ref "R2") (pin "1") (pinfunction "1_1") (pintype "passive"))
      (node (ref "U4") (pin "1") (pinfunction "EN_1") (pintype "passive"))
      (node (ref "U4") (pin "4") (pinfunction "Vin_4") (pintype "passive"))
    )
    (net (code "83") (name "VCC_12V") (class "Default")
      (node (ref "C2") (pin "1") (pinfunction "1_1") (pintype "passive"))
      (node (ref "C3") (pin "1") (pinfunction "1_1") (pintype "passive"))
      (node (ref "D1") (pin "K") (pinfunction "K_K") (pintype "passive"))
      (node (ref "EC1") (pin "1") (pinfunction "1_1") (pintype "passive"))
      (node (ref "EC2") (pin "1") (pinfunction "1_1") (pintype "passive"))
      (node (ref "L2") (pin "2") (pinfunction "2_2") (pintype "passive"))
      (node (ref "R16") (pin "2") (pinfunction "2_2") (pintype "passive"))
      (node (ref "U1") (pin "1") (pinfunction "IN_1") (pintype "input"))
      (node (ref "U2") (pin "8") (pinfunction "Vin_8") (pintype "power_in"))
    )
    (net (code "84") (name "VCC_24V") (class "Default")
      (node (ref "C5") (pin "1") (pinfunction "1_1") (pintype "passive"))
      (node (ref "D3") (pin "K") (pinfunction "K_K") (pintype "passive"))
      (node (ref "D4") (pin "K") (pinfunction "K_K") (pintype "passive"))
      (node (ref "EC5") (pin "1") (pinfunction "1_1") (pintype "passive"))
      (node (ref "R4") (pin "2") (pinfunction "2_2") (pintype "passive"))
      (node (ref "U7") (pin "6") (pinfunction "6_6") (pintype "passive"))
      (node (ref "U8") (pin "6") (pinfunction "6_6") (pintype "passive"))
    )
    (net (code "85") (name "VCC_24V_A") (class "Default")
      (node (ref "D7") (pin "K") (pinfunction "K_K") (pintype "passive"))
      (node (ref "R33") (pin "1") (pinfunction "1_1") (pintype "passive"))
      (node (ref "R34") (pin "1") (pinfunction "1_1") (pintype "passive"))
      (node (ref "U7") (pin "4") (pinfunction "4_4") (pintype "passive"))
    )
    (net (code "86") (name "VCC_24V_B") (class "Default")
      (node (ref "D8") (pin "K") (pinfunction "K_K") (pintype "passive"))
      (node (ref "R24") (pin "1") (pinfunction "1_1") (pintype "passive"))
      (node (ref "R25") (pin "1") (pinfunction "1_1") (pintype "passive"))
      (node (ref "U8") (pin "4") (pinfunction "4_4") (pintype "passive"))
    )
    (net (code "87") (name "unconnected-(J3-Pad3)") (class "Default")
      (node (ref "J3") (pin "3") (pinfunction "3_3") (pintype "passive"))
    )
    (net (code "88") (name "unconnected-(J6-Pad1)") (class "Default")
      (node (ref "J6") (pin "1") (pinfunction "1_1") (pintype "passive"))
    )
    (net (code "89") (name "unconnected-(J6-Pad4)") (class "Default")
      (node (ref "J6") (pin "4") (pinfunction "4_4") (pintype "passive"))
    )
    (net (code "90") (name "unconnected-(J6-Pad6)") (class "Default")
      (node (ref "J6") (pin "6") (pinfunction "6_6") (pintype "passive"))
    )
    (net (code "91") (name "unconnected-(J6-Pad7)") (class "Default")
      (node (ref "J6") (pin "7") (pinfunction "7_7") (pintype "passive"))
    )
    (net (code "92") (name "unconnected-(J6-Pad8)") (class "Default")
      (node (ref "J6") (pin "8") (pinfunction "8_8") (pintype "passive"))
    )
    (net (code "93") (name "unconnected-(J6-Pad9)") (class "Default")
      (node (ref "J6") (pin "9") (pinfunction "9_9") (pintype "passive"))
    )
    (net (code "94") (name "unconnected-(U13-R2OUT-Pad9)") (class "Default")
      (node (ref "U13") (pin "9") (pinfunction "R2OUT_9") (pintype "output"))
    )
    (net (code "95") (name "unconnected-(U13-RS232OUT2-Pad7)") (class "Default")
      (node (ref "U13") (pin "7") (pinfunction "RS232OUT2_7") (pintype "output"))
    )
  )
)
